# extension_board_interface.net
KiCad netlist of a schematic drawn in EAGLE
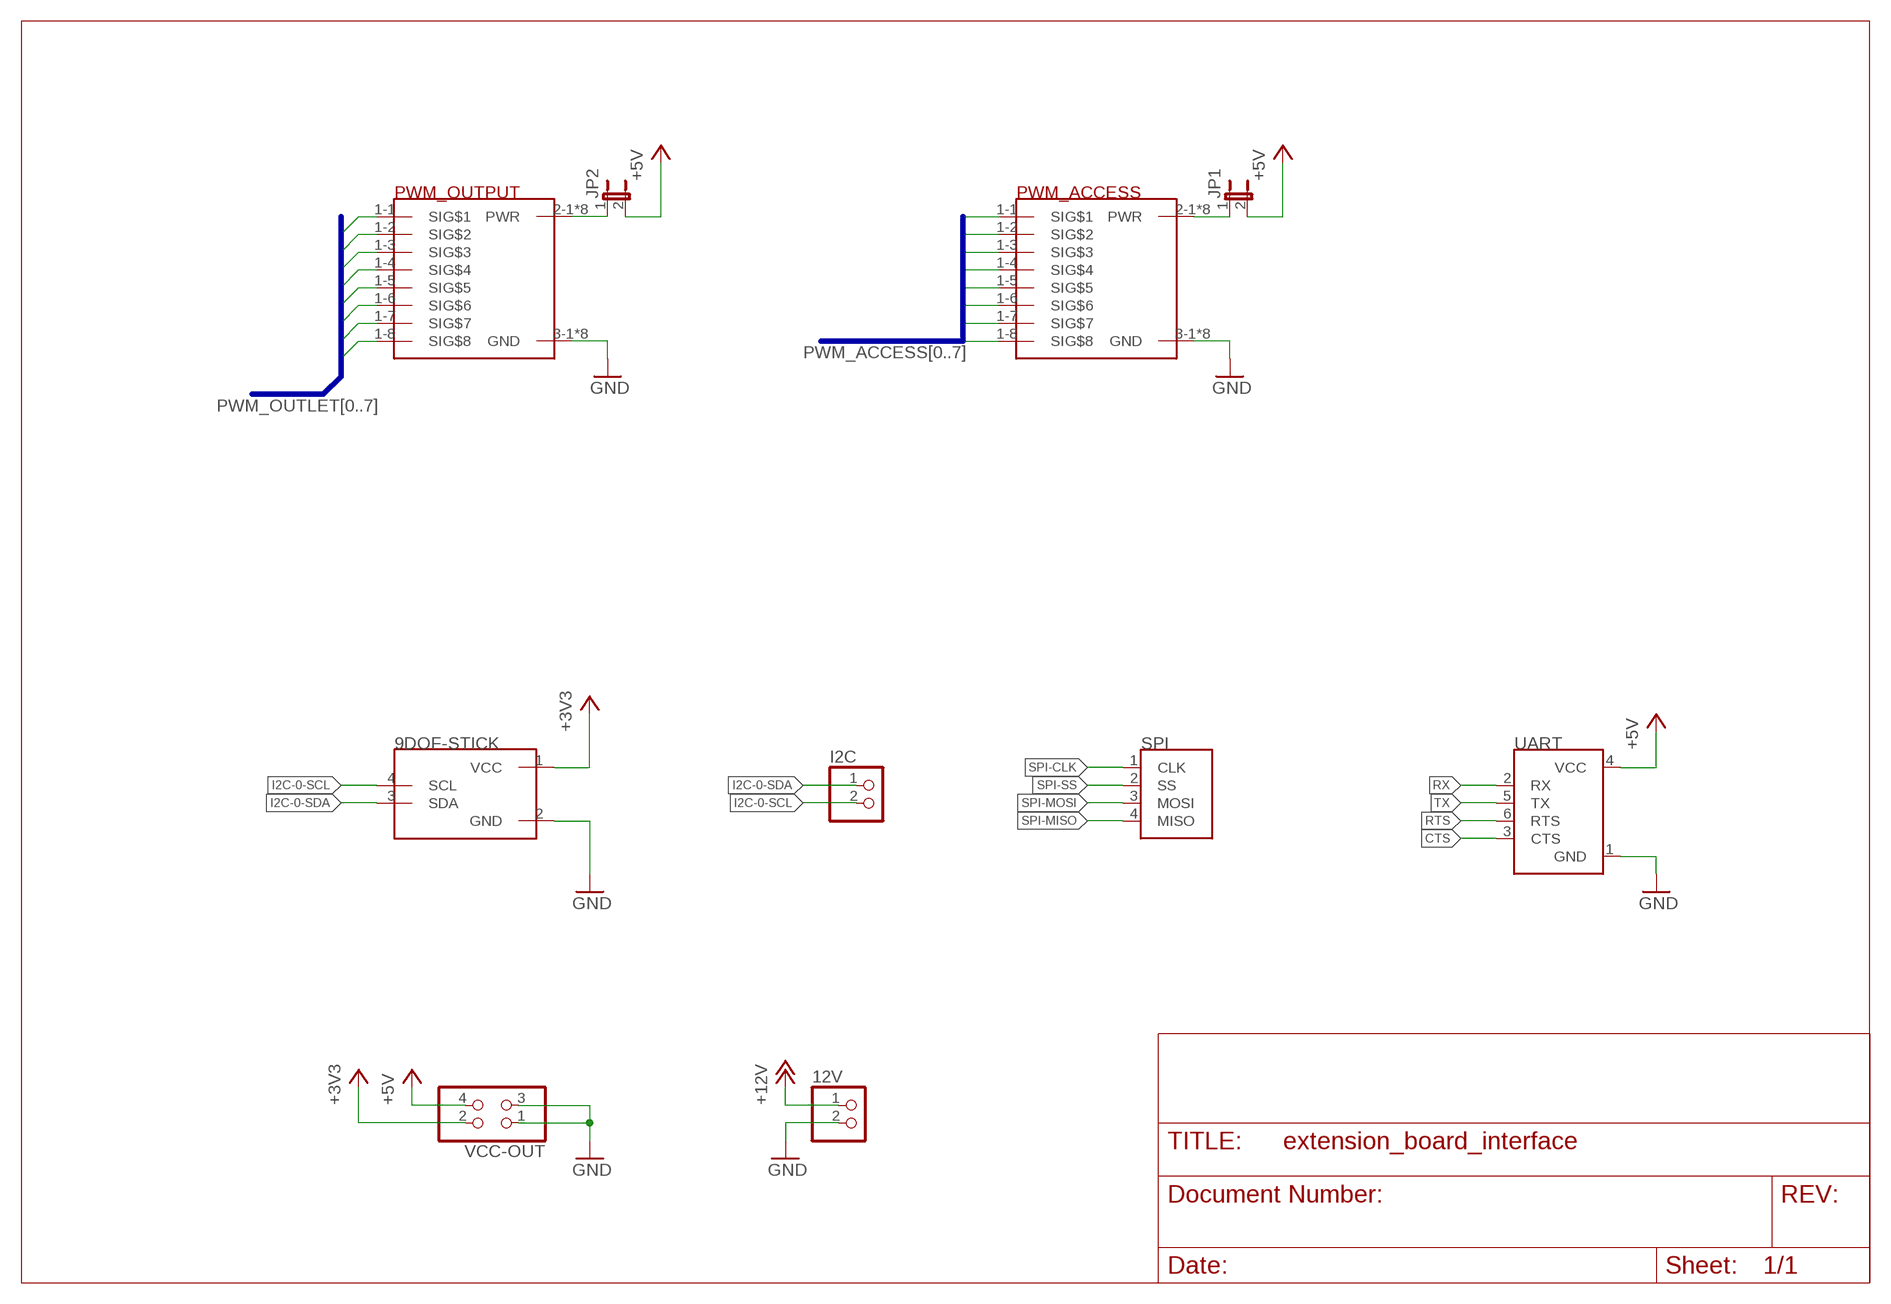
[diagram p0: schematic, sheet 1]

(export (version "E")
  (design (tool "Eeschema 10.0.6"))
  (components
    (comp (ref "9DOF-STICK")
      (value "I2C")
      (footprint "eagle-import:MA04-1")
      (libsource (lib "eagle-import") (part "I2C"))
    )
    (comp (ref "12V")
      (value "PINHD-1X2")
      (footprint "eagle-import:1X02")
      (libsource (lib "eagle-import") (part "PINHD-1X2"))
    )
    (comp (ref "I2C")
      (value "PINHD-1X2")
      (footprint "eagle-import:1X02")
      (libsource (lib "eagle-import") (part "PINHD-1X2"))
    )
    (comp (ref "JP1")
      (value "JP1E")
      (footprint "eagle-import:JP1")
      (libsource (lib "eagle-import") (part "JP1E"))
    )
    (comp (ref "JP2")
      (value "JP1E")
      (footprint "eagle-import:JP1")
      (libsource (lib "eagle-import") (part "JP1E"))
    )
    (comp (ref "PWM_ACCESS")
      (value "8RX")
      (footprint "eagle-import:MA08-3")
      (libsource (lib "eagle-import") (part "8RX"))
    )
    (comp (ref "PWM_OUTPUT")
      (value "8RX")
      (footprint "eagle-import:MA08-3")
      (libsource (lib "eagle-import") (part "8RX"))
    )
    (comp (ref "SPI")
      (value "SPI")
      (footprint "eagle-import:MA04-1")
      (libsource (lib "eagle-import") (part "SPI"))
    )
    (comp (ref "UART")
      (value "UART")
      (footprint "eagle-import:MA03-2")
      (libsource (lib "eagle-import") (part "UART"))
    )
    (comp (ref "VCC-OUT")
      (value "PINHD-2X2")
      (footprint "eagle-import:2X02")
      (libsource (lib "eagle-import") (part "PINHD-2X2"))
    )
  )
  (nets
    (net (code "17") (name "+3V3") (class "Default")
      (node (ref "9DOF-STICK") (pin "1") (pinfunction "VCC_1") (pintype "power_in"))
      (node (ref "VCC-OUT") (pin "2") (pinfunction "2_2") (pintype "passive"))
    )
    (net (code "18") (name "+5V") (class "Default")
      (node (ref "JP1") (pin "2") (pinfunction "2_2") (pintype "passive"))
      (node (ref "JP2") (pin "2") (pinfunction "2_2") (pintype "passive"))
      (node (ref "UART") (pin "4") (pinfunction "VCC_4") (pintype "bidirectional"))
      (node (ref "VCC-OUT") (pin "4") (pinfunction "4_4") (pintype "passive"))
    )
    (net (code "19") (name "+12V") (class "Default")
      (node (ref "12V") (pin "1") (pinfunction "1_1") (pintype "passive"))
    )
    (net (code "22") (name "CTS") (class "Default")
      (node (ref "UART") (pin "3") (pinfunction "CTS_3") (pintype "bidirectional"))
    )
    (net (code "23") (name "GND") (class "Default")
      (node (ref "12V") (pin "2") (pinfunction "2_2") (pintype "passive"))
      (node (ref "9DOF-STICK") (pin "2") (pinfunction "GND_2") (pintype "power_in"))
      (node (ref "PWM_ACCESS") (pin "3-1") (pinfunction "GND_3-1") (pintype "power_in"))
      (node (ref "PWM_ACCESS") (pin "3-2") (pinfunction "GND_3-2") (pintype "power_in"))
      (node (ref "PWM_ACCESS") (pin "3-3") (pinfunction "GND_3-3") (pintype "power_in"))
      (node (ref "PWM_ACCESS") (pin "3-4") (pinfunction "GND_3-4") (pintype "power_in"))
      (node (ref "PWM_ACCESS") (pin "3-5") (pinfunction "GND_3-5") (pintype "power_in"))
      (node (ref "PWM_ACCESS") (pin "3-6") (pinfunction "GND_3-6") (pintype "power_in"))
      (node (ref "PWM_ACCESS") (pin "3-7") (pinfunction "GND_3-7") (pintype "power_in"))
      (node (ref "PWM_ACCESS") (pin "3-8") (pinfunction "GND_3-8") (pintype "power_in"))
      (node (ref "PWM_OUTPUT") (pin "3-1") (pinfunction "GND_3-1") (pintype "power_in"))
      (node (ref "PWM_OUTPUT") (pin "3-2") (pinfunction "GND_3-2") (pintype "power_in"))
      (node (ref "PWM_OUTPUT") (pin "3-3") (pinfunction "GND_3-3") (pintype "power_in"))
      (node (ref "PWM_OUTPUT") (pin "3-4") (pinfunction "GND_3-4") (pintype "power_in"))
      (node (ref "PWM_OUTPUT") (pin "3-5") (pinfunction "GND_3-5") (pintype "power_in"))
      (node (ref "PWM_OUTPUT") (pin "3-6") (pinfunction "GND_3-6") (pintype "power_in"))
      (node (ref "PWM_OUTPUT") (pin "3-7") (pinfunction "GND_3-7") (pintype "power_in"))
      (node (ref "PWM_OUTPUT") (pin "3-8") (pinfunction "GND_3-8") (pintype "power_in"))
      (node (ref "UART") (pin "1") (pinfunction "GND_1") (pintype "bidirectional"))
      (node (ref "VCC-OUT") (pin "1") (pinfunction "1_1") (pintype "passive"))
      (node (ref "VCC-OUT") (pin "3") (pinfunction "3_3") (pintype "passive"))
    )
    (net (code "24") (name "I2C-0-SCL") (class "Default")
      (node (ref "9DOF-STICK") (pin "4") (pinfunction "SCL_4") (pintype "bidirectional"))
      (node (ref "I2C") (pin "2") (pinfunction "2_2") (pintype "passive"))
    )
    (net (code "25") (name "I2C-0-SDA") (class "Default")
      (node (ref "9DOF-STICK") (pin "3") (pinfunction "SDA_3") (pintype "bidirectional"))
      (node (ref "I2C") (pin "1") (pinfunction "1_1") (pintype "passive"))
    )
    (net (code "26") (name "Net-(JP1-Pad1)") (class "Default")
      (node (ref "JP1") (pin "1") (pinfunction "1_1") (pintype "passive"))
      (node (ref "PWM_ACCESS") (pin "2-1") (pinfunction "PWR_2-1") (pintype "power_in"))
      (node (ref "PWM_ACCESS") (pin "2-2") (pinfunction "PWR_2-2") (pintype "power_in"))
      (node (ref "PWM_ACCESS") (pin "2-3") (pinfunction "PWR_2-3") (pintype "power_in"))
      (node (ref "PWM_ACCESS") (pin "2-4") (pinfunction "PWR_2-4") (pintype "power_in"))
      (node (ref "PWM_ACCESS") (pin "2-5") (pinfunction "PWR_2-5") (pintype "power_in"))
      (node (ref "PWM_ACCESS") (pin "2-6") (pinfunction "PWR_2-6") (pintype "power_in"))
      (node (ref "PWM_ACCESS") (pin "2-7") (pinfunction "PWR_2-7") (pintype "power_in"))
      (node (ref "PWM_ACCESS") (pin "2-8") (pinfunction "PWR_2-8") (pintype "power_in"))
    )
    (net (code "27") (name "Net-(JP2-Pad1)") (class "Default")
      (node (ref "JP2") (pin "1") (pinfunction "1_1") (pintype "passive"))
      (node (ref "PWM_OUTPUT") (pin "2-1") (pinfunction "PWR_2-1") (pintype "power_in"))
      (node (ref "PWM_OUTPUT") (pin "2-2") (pinfunction "PWR_2-2") (pintype "power_in"))
      (node (ref "PWM_OUTPUT") (pin "2-3") (pinfunction "PWR_2-3") (pintype "power_in"))
      (node (ref "PWM_OUTPUT") (pin "2-4") (pinfunction "PWR_2-4") (pintype "power_in"))
      (node (ref "PWM_OUTPUT") (pin "2-5") (pinfunction "PWR_2-5") (pintype "power_in"))
      (node (ref "PWM_OUTPUT") (pin "2-6") (pinfunction "PWR_2-6") (pintype "power_in"))
      (node (ref "PWM_OUTPUT") (pin "2-7") (pinfunction "PWR_2-7") (pintype "power_in"))
      (node (ref "PWM_OUTPUT") (pin "2-8") (pinfunction "PWR_2-8") (pintype "power_in"))
    )
    (net (code "28") (name "RTS") (class "Default")
      (node (ref "UART") (pin "6") (pinfunction "RTS_6") (pintype "bidirectional"))
    )
    (net (code "29") (name "RX") (class "Default")
      (node (ref "UART") (pin "2") (pinfunction "RX_2") (pintype "bidirectional"))
    )
    (net (code "30") (name "SPI-CLK") (class "Default")
      (node (ref "SPI") (pin "1") (pinfunction "CLK_1") (pintype "bidirectional"))
    )
    (net (code "31") (name "SPI-MISO") (class "Default")
      (node (ref "SPI") (pin "4") (pinfunction "MISO_4") (pintype "bidirectional"))
    )
    (net (code "32") (name "SPI-MOSI") (class "Default")
      (node (ref "SPI") (pin "3") (pinfunction "MOSI_3") (pintype "bidirectional"))
    )
    (net (code "33") (name "SPI-SS") (class "Default")
      (node (ref "SPI") (pin "2") (pinfunction "SS_2") (pintype "bidirectional"))
    )
    (net (code "34") (name "TX") (class "Default")
      (node (ref "UART") (pin "5") (pinfunction "TX_5") (pintype "bidirectional"))
    )
    (net (code "35") (name "unconnected-(PWM_ACCESS-SIG$1-Pad1-1)") (class "Default")
      (node (ref "PWM_ACCESS") (pin "1-1") (pinfunction "SIG$1_1-1") (pintype "bidirectional"))
    )
    (net (code "36") (name "unconnected-(PWM_ACCESS-SIG$2-Pad1-2)") (class "Default")
      (node (ref "PWM_ACCESS") (pin "1-2") (pinfunction "SIG$2_1-2") (pintype "bidirectional"))
    )
    (net (code "37") (name "unconnected-(PWM_ACCESS-SIG$3-Pad1-3)") (class "Default")
      (node (ref "PWM_ACCESS") (pin "1-3") (pinfunction "SIG$3_1-3") (pintype "bidirectional"))
    )
    (net (code "38") (name "unconnected-(PWM_ACCESS-SIG$4-Pad1-4)") (class "Default")
      (node (ref "PWM_ACCESS") (pin "1-4") (pinfunction "SIG$4_1-4") (pintype "bidirectional"))
    )
    (net (code "39") (name "unconnected-(PWM_ACCESS-SIG$5-Pad1-5)") (class "Default")
      (node (ref "PWM_ACCESS") (pin "1-5") (pinfunction "SIG$5_1-5") (pintype "bidirectional"))
    )
    (net (code "40") (name "unconnected-(PWM_ACCESS-SIG$6-Pad1-6)") (class "Default")
      (node (ref "PWM_ACCESS") (pin "1-6") (pinfunction "SIG$6_1-6") (pintype "bidirectional"))
    )
    (net (code "41") (name "unconnected-(PWM_ACCESS-SIG$7-Pad1-7)") (class "Default")
      (node (ref "PWM_ACCESS") (pin "1-7") (pinfunction "SIG$7_1-7") (pintype "bidirectional"))
    )
    (net (code "42") (name "unconnected-(PWM_ACCESS-SIG$8-Pad1-8)") (class "Default")
      (node (ref "PWM_ACCESS") (pin "1-8") (pinfunction "SIG$8_1-8") (pintype "bidirectional"))
    )
    (net (code "43") (name "unconnected-(PWM_OUTPUT-SIG$1-Pad1-1)") (class "Default")
      (node (ref "PWM_OUTPUT") (pin "1-1") (pinfunction "SIG$1_1-1") (pintype "bidirectional"))
    )
    (net (code "44") (name "unconnected-(PWM_OUTPUT-SIG$2-Pad1-2)") (class "Default")
      (node (ref "PWM_OUTPUT") (pin "1-2") (pinfunction "SIG$2_1-2") (pintype "bidirectional"))
    )
    (net (code "45") (name "unconnected-(PWM_OUTPUT-SIG$3-Pad1-3)") (class "Default")
      (node (ref "PWM_OUTPUT") (pin "1-3") (pinfunction "SIG$3_1-3") (pintype "bidirectional"))
    )
    (net (code "46") (name "unconnected-(PWM_OUTPUT-SIG$4-Pad1-4)") (class "Default")
      (node (ref "PWM_OUTPUT") (pin "1-4") (pinfunction "SIG$4_1-4") (pintype "bidirectional"))
    )
    (net (code "47") (name "unconnected-(PWM_OUTPUT-SIG$5-Pad1-5)") (class "Default")
      (node (ref "PWM_OUTPUT") (pin "1-5") (pinfunction "SIG$5_1-5") (pintype "bidirectional"))
    )
    (net (code "48") (name "unconnected-(PWM_OUTPUT-SIG$6-Pad1-6)") (class "Default")
      (node (ref "PWM_OUTPUT") (pin "1-6") (pinfunction "SIG$6_1-6") (pintype "bidirectional"))
    )
    (net (code "49") (name "unconnected-(PWM_OUTPUT-SIG$7-Pad1-7)") (class "Default")
      (node (ref "PWM_OUTPUT") (pin "1-7") (pinfunction "SIG$7_1-7") (pintype "bidirectional"))
    )
    (net (code "50") (name "unconnected-(PWM_OUTPUT-SIG$8-Pad1-8)") (class "Default")
      (node (ref "PWM_OUTPUT") (pin "1-8") (pinfunction "SIG$8_1-8") (pintype "bidirectional"))
    )
  )
)
